# 2013_PerfXBee.net
KiCad netlist of a schematic drawn in Altium Designer
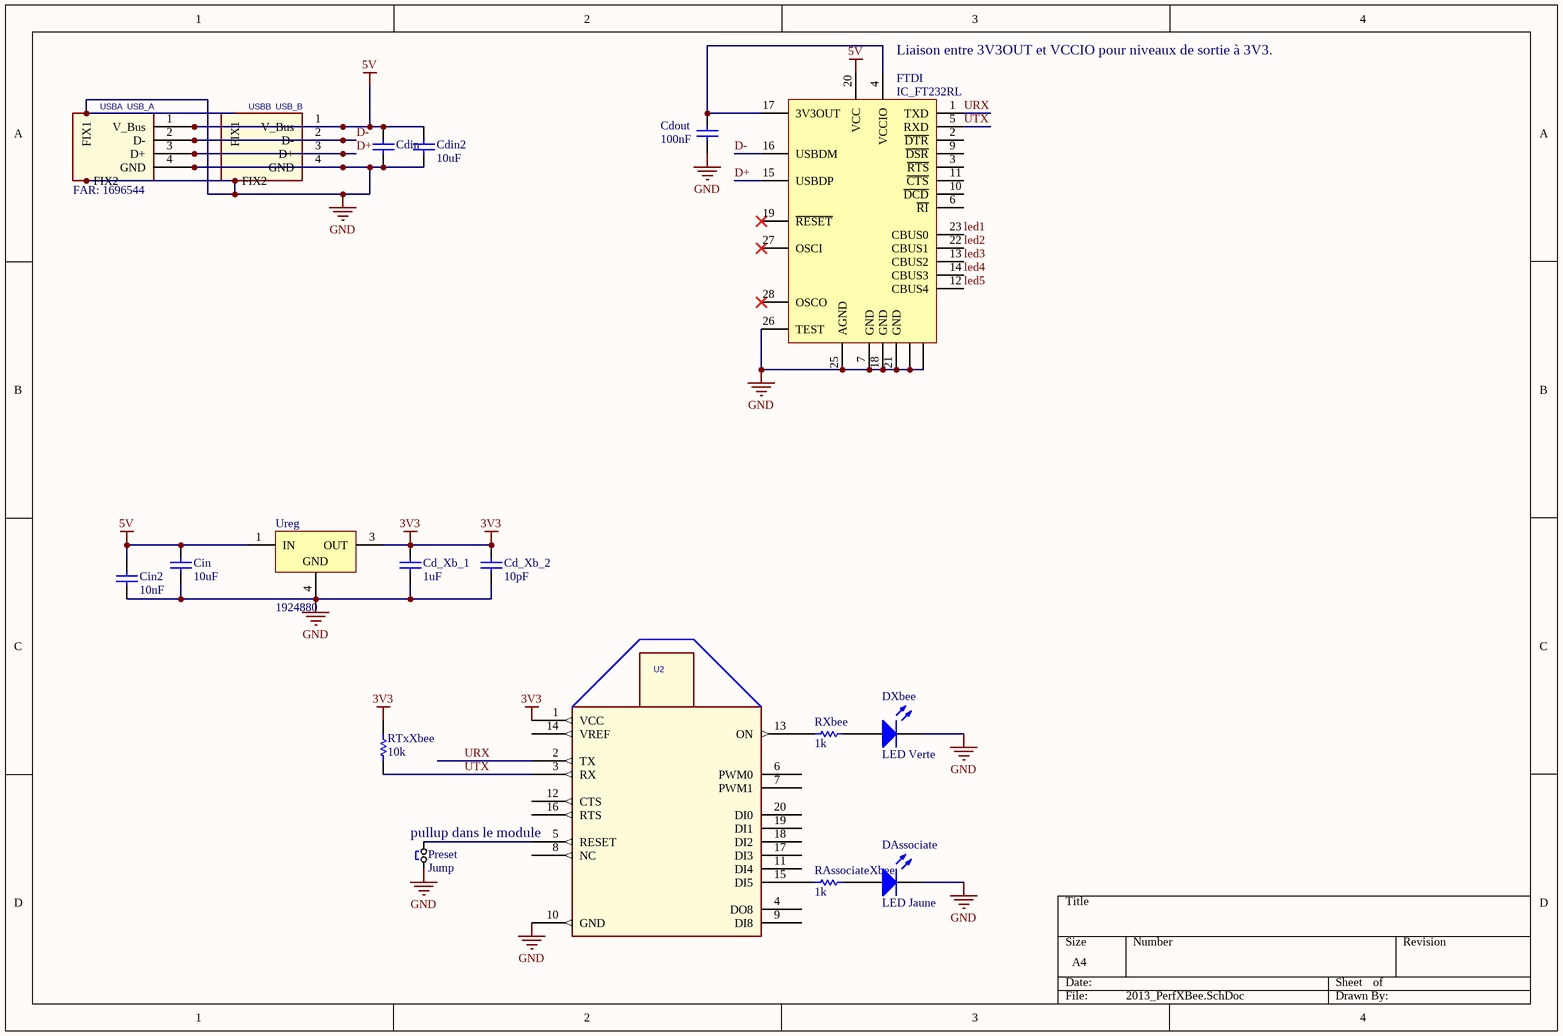
[diagram p0: 2013_PerfXBee.SchDoc]

(export (version "E")
  (design (tool "Eeschema 10.0.6"))
  (components
    (comp (ref "Cdin")
      (value "100nF")
      (footprint "C0603_N")
      (description "Capacitor")
      (fields (field (name "PUBLISHER") "Damien GUITTON"))
      (libsource (lib "") (part "Capacitor_1"))
    )
    (comp (ref "Cdin2")
      (value "10uF")
      (footprint "C1206_N")
      (description "Capacitor")
      (fields (field (name "PUBLISHER") "Altium Limited"))
      (libsource (lib "DG_Condensateur") (part "Capacitor"))
    )
    (comp (ref "Cdout")
      (value "100nF")
      (footprint "C0603_N")
      (description "Capacitor")
      (fields (field (name "PUBLISHER") "Damien GUITTON"))
      (libsource (lib "DG_discret") (part "Capacitor"))
    )
    (comp (ref "Cd_Xb_1")
      (value "1uF")
      (footprint "C0805_N")
      (description "Capacitor")
      (fields (field (name "PUBLISHER") "Altium Limited"))
      (libsource (lib "_ROBOT") (part "Condensateur"))
    )
    (comp (ref "Cd_Xb_2")
      (value "10pF")
      (footprint "C0805_N")
      (description "Capacitor")
      (fields (field (name "PUBLISHER") "Altium Limited"))
      (libsource (lib "_ROBOT") (part "Condensateur"))
    )
    (comp (ref "Cin")
      (value "10uF")
      (footprint "C1206_N")
      (description "Capacitor")
      (fields (field (name "PUBLISHER") "Altium Limited"))
      (libsource (lib "DG_Condensateur") (part "Capacitor"))
    )
    (comp (ref "Cin2")
      (value "10nF")
      (footprint "C0805_N")
      (description "Capacitor")
      (fields (field (name "PUBLISHER") "Altium Limited"))
      (libsource (lib "DG_Condensateur") (part "Capacitor"))
    )
    (comp (ref "DAssociate")
      (value "LED Jaune")
      (footprint "LED_0805")
      (description "Typical LED")
      (fields (field (name "PUBLISHER") "Altium Limited"))
      (libsource (lib "_ROBOT") (part "LED"))
    )
    (comp (ref "DXbee")
      (value "LED Verte")
      (footprint "LED_0805")
      (description "Typical LED")
      (fields (field (name "PUBLISHER") "Altium Limited"))
      (libsource (lib "_ROBOT") (part "LED"))
    )
    (comp (ref "FTDI")
      (value "IC_FT232RL")
      (footprint "SSOP28_N")
      (description "FT232R USB UART")
      (libsource (lib "Circuit intégré") (part "IC_FT232RL"))
    )
    (comp (ref "Preset")
      (value "Jump")
      (footprint "HDR1X2")
      (description "Jumper SIP2.54")
      (libsource (lib "Connecteur") (part "Jumper SIP2.54"))
    )
    (comp (ref "RAssociateXbee")
      (value "1k")
      (footprint "R1206_N")
      (description "Resistor")
      (fields (field (name "PUBLISHER") "Altium Limited"))
      (libsource (lib "_ROBOT") (part "Resistor"))
    )
    (comp (ref "RTxXbee")
      (value "10k")
      (footprint "R1206_N")
      (description "Resistor")
      (fields (field (name "PUBLISHER") "Altium Limited"))
      (libsource (lib "_ROBOT") (part "Resistor"))
    )
    (comp (ref "RXbee")
      (value "1k")
      (footprint "R1206_N")
      (description "Resistor")
      (fields (field (name "PUBLISHER") "Altium Limited"))
      (libsource (lib "_ROBOT") (part "Resistor"))
    )
    (comp (ref "U2") (value "XBee") (footprint "MODULE_XBEE") (libsource (lib "*") (part "XBee")))
    (comp (ref "Ureg")
      (value "1924880")
      (footprint "369A-13")
      (description "Three-Terminal Positive Voltage Regulator")
      (fields (field (name "PUBLISHER") "Altium Limited"))
      (libsource (lib "ON Semi Power Mgt Voltage Regulator") (part "MC7805ACD2T"))
    )
    (comp (ref "USBA")
      (value "USB_A")
      (footprint "USB_A_COUDE - FAR1696544")
      (description "FAR1696544")
      (fields (field (name "FAR") "1696544"))
      (libsource (lib "*") (part "USB_B"))
    )
    (comp (ref "USBB") (value "USB_B") (footprint "USB_B_COUDE") (libsource (lib "*") (part "USB_B")))
  )
  (nets
    (net (code "1") (name "/D+") (class "Default")
      (node (ref "FTDI") (pin "15") (pinfunction "USBDP_15") (pintype "passive"))
      (node (ref "USBA") (pin "3") (pinfunction "D+_3") (pintype "passive"))
      (node (ref "USBB") (pin "3") (pinfunction "D+_3") (pintype "passive"))
    )
    (net (code "2") (name "/D-") (class "Default")
      (node (ref "FTDI") (pin "16") (pinfunction "USBDM_16") (pintype "passive"))
      (node (ref "USBA") (pin "2") (pinfunction "D-_2") (pintype "passive"))
      (node (ref "USBB") (pin "2") (pinfunction "D-_2") (pintype "passive"))
    )
    (net (code "3") (name "/URX") (class "Default")
      (node (ref "FTDI") (pin "1") (pinfunction "TXD_1") (pintype "passive"))
      (node (ref "U2") (pin "2") (pinfunction "TX_2") (pintype "output"))
    )
    (net (code "4") (name "/UTX") (class "Default")
      (node (ref "FTDI") (pin "5") (pinfunction "RXD_5") (pintype "passive"))
      (node (ref "RTxXbee") (pin "2") (pinfunction "2_2") (pintype "passive"))
      (node (ref "U2") (pin "3") (pinfunction "RX_3") (pintype "output"))
    )
    (net (code "5") (name "/led1") (class "Default")
      (node (ref "FTDI") (pin "23") (pinfunction "CBUS0_23") (pintype "passive"))
    )
    (net (code "6") (name "/led2") (class "Default")
      (node (ref "FTDI") (pin "22") (pinfunction "CBUS1_22") (pintype "passive"))
    )
    (net (code "7") (name "/led3") (class "Default")
      (node (ref "FTDI") (pin "13") (pinfunction "CBUS2_13") (pintype "passive"))
    )
    (net (code "8") (name "/led4") (class "Default")
      (node (ref "FTDI") (pin "14") (pinfunction "CBUS3_14") (pintype "passive"))
    )
    (net (code "9") (name "/led5") (class "Default")
      (node (ref "FTDI") (pin "12") (pinfunction "CBUS4_12") (pintype "passive"))
    )
    (net (code "10") (name "3V3") (class "Default")
      (node (ref "Cd_Xb_1") (pin "2") (pinfunction "2_2") (pintype "passive"))
      (node (ref "Cd_Xb_2") (pin "2") (pinfunction "2_2") (pintype "passive"))
      (node (ref "RTxXbee") (pin "1") (pinfunction "1_1") (pintype "passive"))
      (node (ref "U2") (pin "1") (pinfunction "VCC_1") (pintype "output"))
      (node (ref "Ureg") (pin "3") (pinfunction "OUT_3") (pintype "power_in"))
    )
    (net (code "11") (name "5V") (class "Default")
      (node (ref "Cdin") (pin "2") (pinfunction "2_2") (pintype "passive"))
      (node (ref "Cdin2") (pin "2") (pinfunction "2_2") (pintype "passive"))
      (node (ref "Cin") (pin "2") (pinfunction "2_2") (pintype "passive"))
      (node (ref "Cin2") (pin "2") (pinfunction "2_2") (pintype "passive"))
      (node (ref "FTDI") (pin "20") (pinfunction "VCC_20") (pintype "passive"))
      (node (ref "USBA") (pin "1") (pinfunction "V_Bus_1") (pintype "passive"))
      (node (ref "USBB") (pin "1") (pinfunction "V_Bus_1") (pintype "passive"))
      (node (ref "Ureg") (pin "1") (pinfunction "IN_1") (pintype "power_in"))
    )
    (net (code "12") (name "GND") (class "Default")
      (node (ref "Cd_Xb_1") (pin "1") (pinfunction "1_1") (pintype "passive"))
      (node (ref "Cd_Xb_2") (pin "1") (pinfunction "1_1") (pintype "passive"))
      (node (ref "Cdin") (pin "1") (pinfunction "1_1") (pintype "passive"))
      (node (ref "Cdin2") (pin "1") (pinfunction "1_1") (pintype "passive"))
      (node (ref "Cdout") (pin "1") (pinfunction "1_1") (pintype "passive"))
      (node (ref "Cin") (pin "1") (pinfunction "1_1") (pintype "passive"))
      (node (ref "Cin2") (pin "1") (pinfunction "1_1") (pintype "passive"))
      (node (ref "DAssociate") (pin "2") (pinfunction "K_2") (pintype "passive"))
      (node (ref "DXbee") (pin "2") (pinfunction "K_2") (pintype "passive"))
      (node (ref "FTDI") (pin "18") (pinfunction "GND_18") (pintype "passive"))
      (node (ref "FTDI") (pin "21") (pinfunction "GND_21") (pintype "passive"))
      (node (ref "FTDI") (pin "24") (pinfunction "NC_24") (pintype "passive"))
      (node (ref "FTDI") (pin "25") (pinfunction "AGND_25") (pintype "passive"))
      (node (ref "FTDI") (pin "26") (pinfunction "TEST_26") (pintype "passive"))
      (node (ref "FTDI") (pin "7") (pinfunction "GND_7") (pintype "passive"))
      (node (ref "FTDI") (pin "8") (pinfunction "NC_8") (pintype "passive"))
      (node (ref "Preset") (pin "1") (pinfunction "1_1") (pintype "passive"))
      (node (ref "U2") (pin "10") (pinfunction "GND_10") (pintype "output"))
      (node (ref "USBA") (pin "4") (pinfunction "GND_4") (pintype "passive"))
      (node (ref "USBA") (pin "FIX1") (pinfunction "FIX1_FIX1") (pintype "passive"))
      (node (ref "USBA") (pin "FIX2") (pinfunction "FIX2_FIX2") (pintype "passive"))
      (node (ref "USBB") (pin "4") (pinfunction "GND_4") (pintype "passive"))
      (node (ref "USBB") (pin "FIX1") (pinfunction "FIX1_FIX1") (pintype "passive"))
      (node (ref "USBB") (pin "FIX2") (pinfunction "FIX2_FIX2") (pintype "passive"))
      (node (ref "Ureg") (pin "4") (pinfunction "GND_4") (pintype "power_in"))
    )
    (net (code "13") (name "Net-(DAssociate-A)") (class "Default")
      (node (ref "DAssociate") (pin "1") (pinfunction "A_1") (pintype "passive"))
      (node (ref "RAssociateXbee") (pin "2") (pinfunction "2_2") (pintype "passive"))
    )
    (net (code "14") (name "Net-(DXbee-A)") (class "Default")
      (node (ref "DXbee") (pin "1") (pinfunction "A_1") (pintype "passive"))
      (node (ref "RXbee") (pin "2") (pinfunction "2_2") (pintype "passive"))
    )
    (net (code "15") (name "Net-(FTDI-3V3OUT)") (class "Default")
      (node (ref "Cdout") (pin "2") (pinfunction "2_2") (pintype "passive"))
      (node (ref "FTDI") (pin "17") (pinfunction "3V3OUT_17") (pintype "passive"))
      (node (ref "FTDI") (pin "4") (pinfunction "VCCIO_4") (pintype "passive"))
    )
    (net (code "16") (name "Net-(U2-DI5)") (class "Default")
      (node (ref "RAssociateXbee") (pin "1") (pinfunction "1_1") (pintype "passive"))
      (node (ref "U2") (pin "15") (pinfunction "DI5_15") (pintype "passive"))
    )
    (net (code "17") (name "Net-(U2-ON)") (class "Default")
      (node (ref "RXbee") (pin "1") (pinfunction "1_1") (pintype "passive"))
      (node (ref "U2") (pin "13") (pinfunction "ON_13") (pintype "output"))
    )
    (net (code "18") (name "Net-(U2-RESET)") (class "Default")
      (node (ref "Preset") (pin "2") (pinfunction "2_2") (pintype "passive"))
      (node (ref "U2") (pin "5") (pinfunction "RESET_5") (pintype "output"))
    )
    (net (code "19") (name "unconnected-(FTDI-OSCI-Pad27)") (class "Default")
      (node (ref "FTDI") (pin "27") (pinfunction "OSCI_27") (pintype "passive+no_connect"))
    )
    (net (code "20") (name "unconnected-(FTDI-OSCO-Pad28)") (class "Default")
      (node (ref "FTDI") (pin "28") (pinfunction "OSCO_28") (pintype "passive+no_connect"))
    )
    (net (code "21") (name "unconnected-(FTDI-~{CTS}-Pad11)") (class "Default")
      (node (ref "FTDI") (pin "11") (pinfunction "~{CTS}_11") (pintype "passive"))
    )
    (net (code "22") (name "unconnected-(FTDI-~{DCD}-Pad10)") (class "Default")
      (node (ref "FTDI") (pin "10") (pinfunction "~{DCD}_10") (pintype "passive"))
    )
    (net (code "23") (name "unconnected-(FTDI-~{DSR}-Pad9)") (class "Default")
      (node (ref "FTDI") (pin "9") (pinfunction "~{DSR}_9") (pintype "passive"))
    )
    (net (code "24") (name "unconnected-(FTDI-~{DTR}-Pad2)") (class "Default")
      (node (ref "FTDI") (pin "2") (pinfunction "~{DTR}_2") (pintype "passive"))
    )
    (net (code "25") (name "unconnected-(FTDI-~{RESET}-Pad19)") (class "Default")
      (node (ref "FTDI") (pin "19") (pinfunction "~{RESET}_19") (pintype "passive+no_connect"))
    )
    (net (code "26") (name "unconnected-(FTDI-~{RI}-Pad6)") (class "Default")
      (node (ref "FTDI") (pin "6") (pinfunction "~{RI}_6") (pintype "passive"))
    )
    (net (code "27") (name "unconnected-(FTDI-~{RTS}-Pad3)") (class "Default")
      (node (ref "FTDI") (pin "3") (pinfunction "~{RTS}_3") (pintype "passive"))
    )
    (net (code "28") (name "unconnected-(U2-CTS-Pad12)") (class "Default")
      (node (ref "U2") (pin "12") (pinfunction "CTS_12") (pintype "output"))
    )
    (net (code "29") (name "unconnected-(U2-DI0-Pad20)") (class "Default")
      (node (ref "U2") (pin "20") (pinfunction "DI0_20") (pintype "passive"))
    )
    (net (code "30") (name "unconnected-(U2-DI1-Pad19)") (class "Default")
      (node (ref "U2") (pin "19") (pinfunction "DI1_19") (pintype "passive"))
    )
    (net (code "31") (name "unconnected-(U2-DI2-Pad18)") (class "Default")
      (node (ref "U2") (pin "18") (pinfunction "DI2_18") (pintype "passive"))
    )
    (net (code "32") (name "unconnected-(U2-DI3-Pad17)") (class "Default")
      (node (ref "U2") (pin "17") (pinfunction "DI3_17") (pintype "passive"))
    )
    (net (code "33") (name "unconnected-(U2-DI4-Pad11)") (class "Default")
      (node (ref "U2") (pin "11") (pinfunction "DI4_11") (pintype "passive"))
    )
    (net (code "34") (name "unconnected-(U2-DI8-Pad9)") (class "Default")
      (node (ref "U2") (pin "9") (pinfunction "DI8_9") (pintype "passive"))
    )
    (net (code "35") (name "unconnected-(U2-DO8-Pad4)") (class "Default")
      (node (ref "U2") (pin "4") (pinfunction "DO8_4") (pintype "passive"))
    )
    (net (code "36") (name "unconnected-(U2-NC-Pad8)") (class "Default")
      (node (ref "U2") (pin "8") (pinfunction "NC_8") (pintype "output"))
    )
    (net (code "37") (name "unconnected-(U2-PWM0-Pad6)") (class "Default")
      (node (ref "U2") (pin "6") (pinfunction "PWM0_6") (pintype "passive"))
    )
    (net (code "38") (name "unconnected-(U2-PWM1-Pad7)") (class "Default")
      (node (ref "U2") (pin "7") (pinfunction "PWM1_7") (pintype "passive"))
    )
    (net (code "39") (name "unconnected-(U2-RTS-Pad16)") (class "Default")
      (node (ref "U2") (pin "16") (pinfunction "RTS_16") (pintype "output"))
    )
    (net (code "40") (name "unconnected-(U2-VREF-Pad14)") (class "Default")
      (node (ref "U2") (pin "14") (pinfunction "VREF_14") (pintype "output"))
    )
  )
)
